# MainPCB.net
KiCad netlist of a schematic drawn in EAGLE
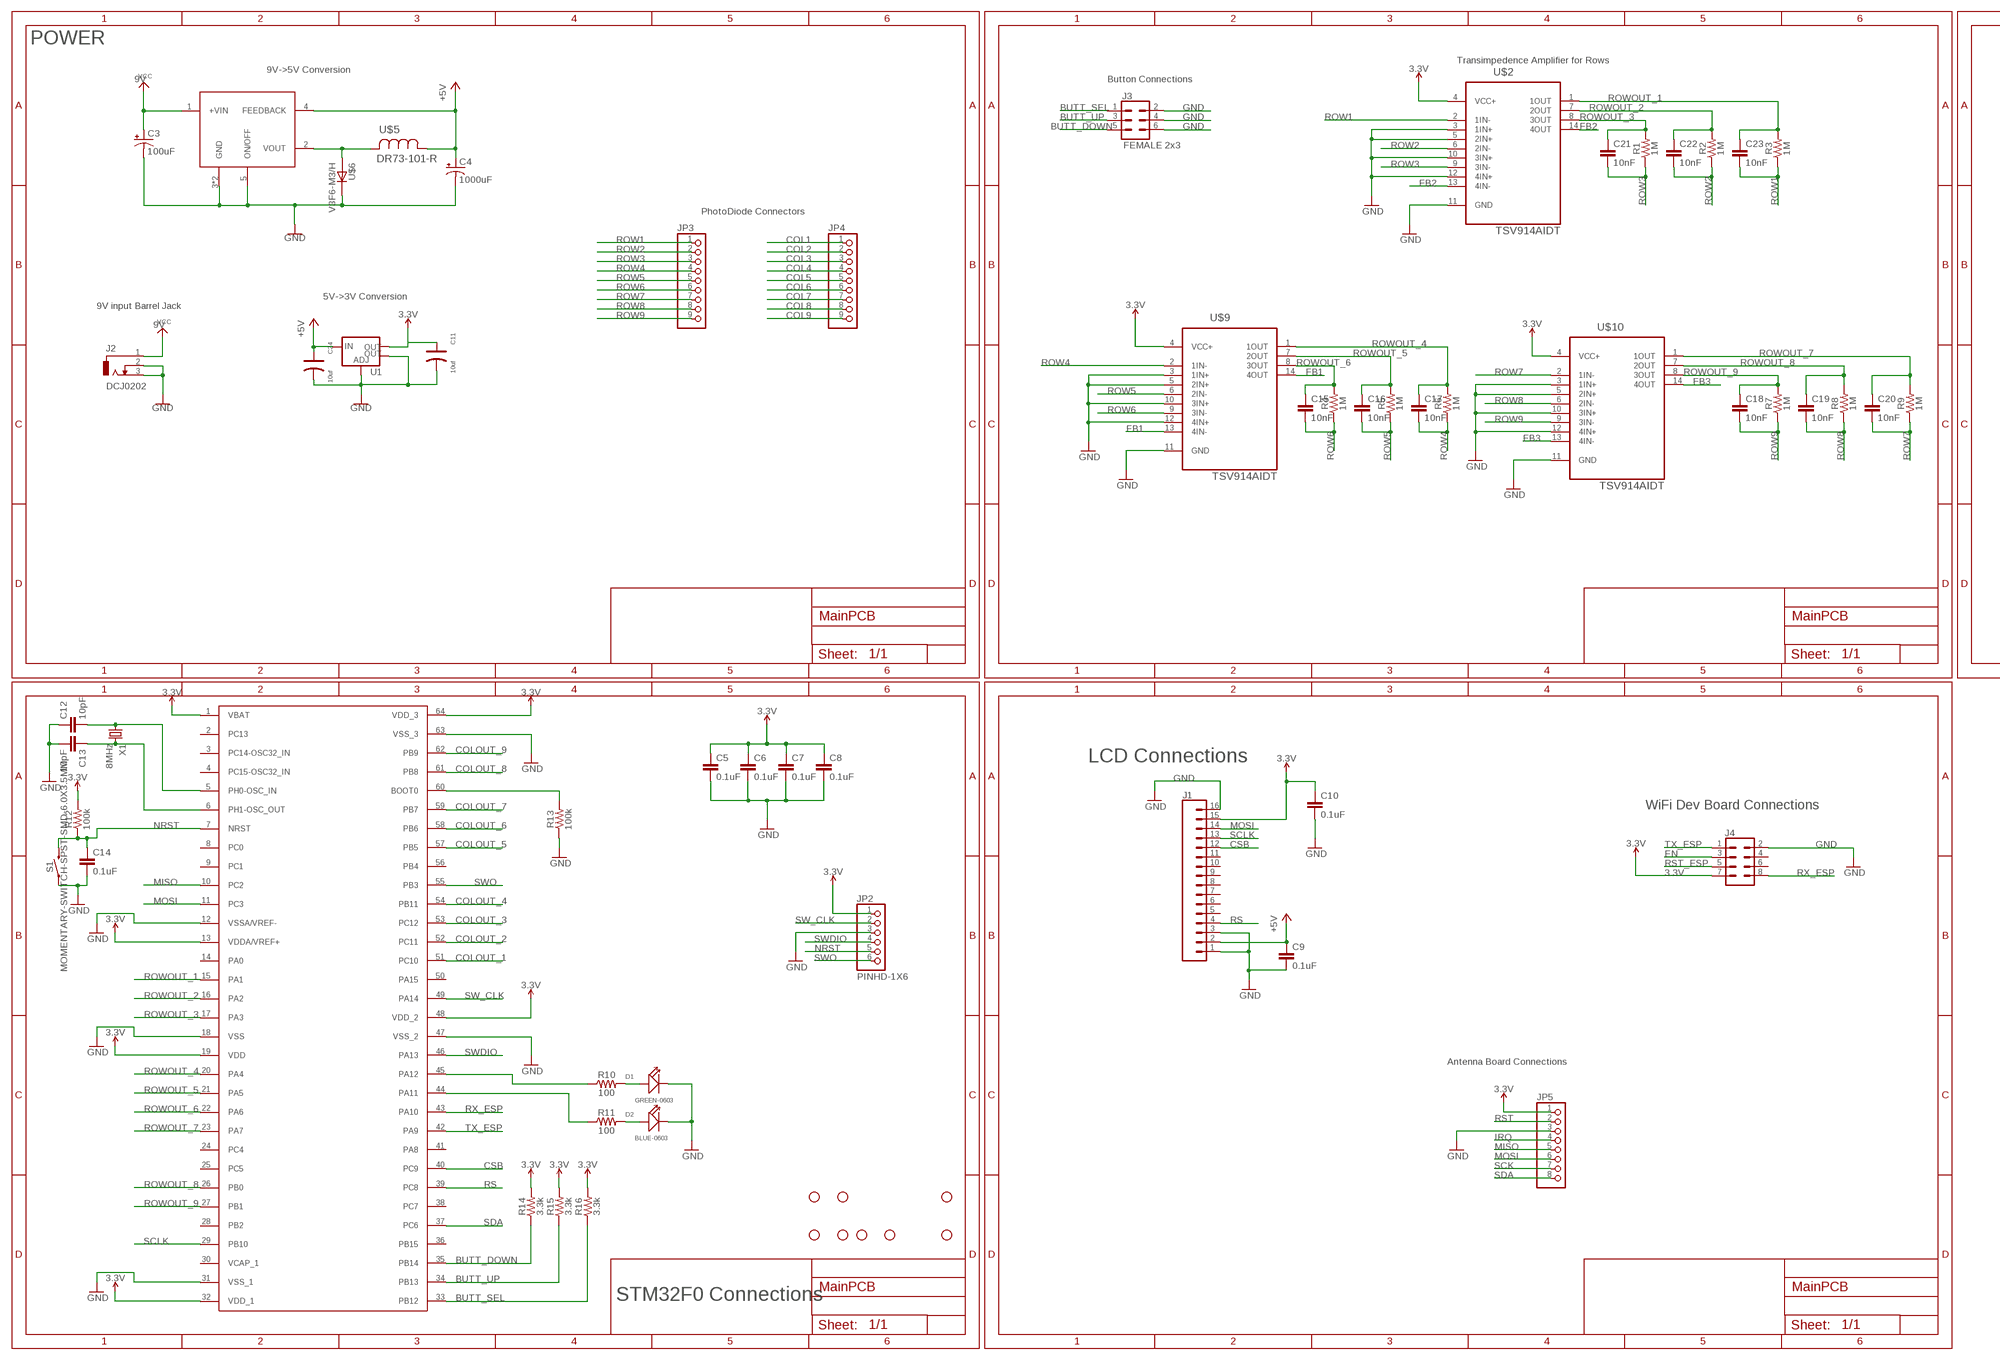
[diagram p0: schematic, sheet 1, part 1 of 2]
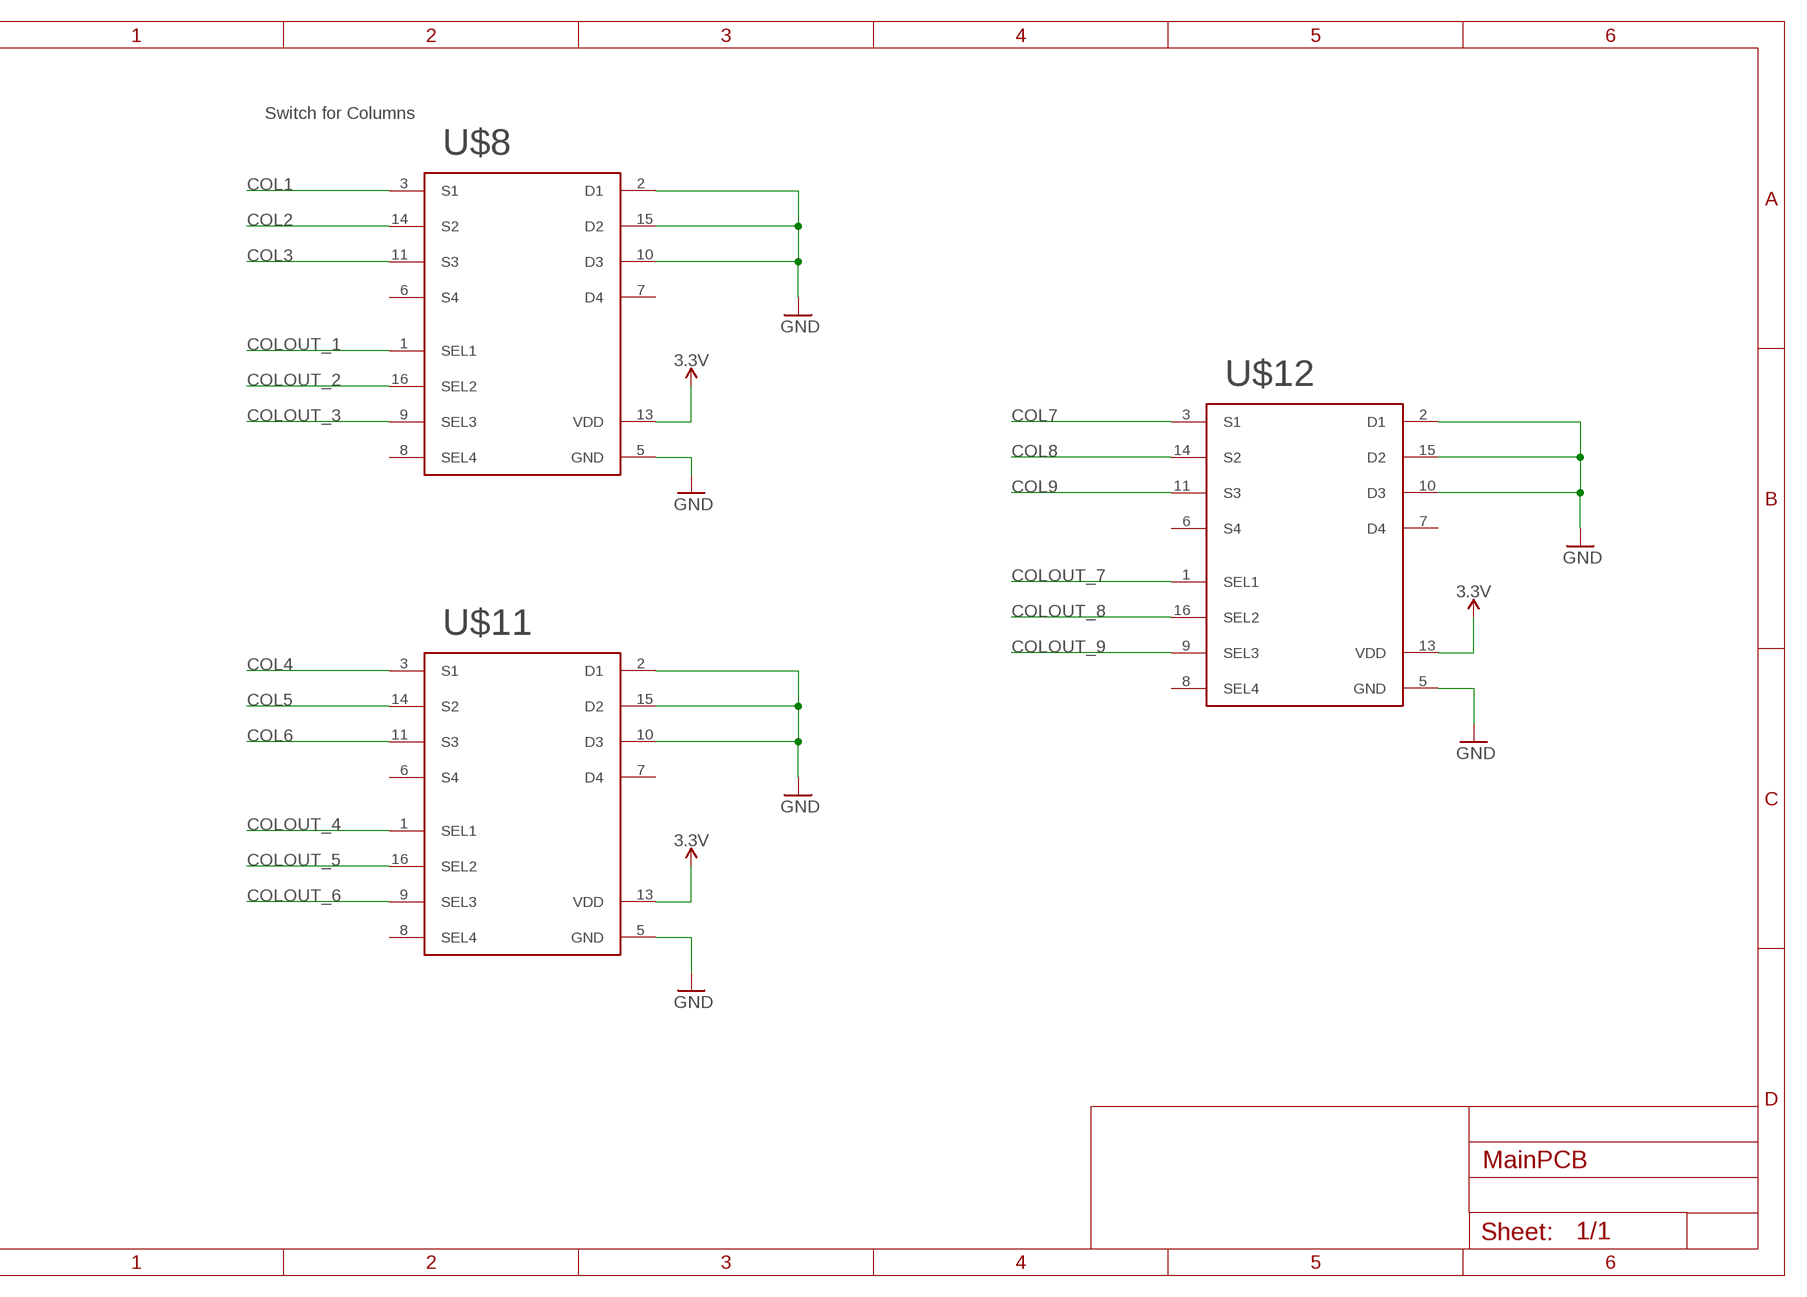
[diagram p1: schematic, sheet 1, part 2 of 2]

(export (version "E")
  (design (tool "Eeschema 10.0.6"))
  (components
    (comp (ref "C3")
      (value "100uF")
      (footprint "eagle-import:PANASONIC_D")
      (libsource (lib "eagle-import") (part "100UF-POLAR-25V-20%(ELEC)"))
    )
    (comp (ref "C4")
      (value "1000uF")
      (footprint "eagle-import:PANASONIC_D")
      (libsource (lib "eagle-import") (part "100UF-POLAR-25V-20%(ELEC)"))
    )
    (comp (ref "C5")
      (value "0.1uF")
      (footprint "eagle-import:0603")
      (libsource (lib "eagle-import") (part "0.1UF-0603-100V-10%"))
    )
    (comp (ref "C6")
      (value "0.1uF")
      (footprint "eagle-import:0603")
      (libsource (lib "eagle-import") (part "0.1UF-0603-100V-10%"))
    )
    (comp (ref "C7")
      (value "0.1uF")
      (footprint "eagle-import:0603")
      (libsource (lib "eagle-import") (part "0.1UF-0603-100V-10%"))
    )
    (comp (ref "C8")
      (value "0.1uF")
      (footprint "eagle-import:0603")
      (libsource (lib "eagle-import") (part "0.1UF-0603-100V-10%"))
    )
    (comp (ref "C9")
      (value "0.1uF")
      (footprint "eagle-import:0603")
      (libsource (lib "eagle-import") (part "0.1UF-0603-100V-10%"))
    )
    (comp (ref "C10")
      (value "0.1uF")
      (footprint "eagle-import:0603")
      (libsource (lib "eagle-import") (part "0.1UF-0603-100V-10%"))
    )
    (comp (ref "C11")
      (value "10uf")
      (footprint "eagle-import:AVX-A")
      (fields (field (name "MPN") "TAJA106K010RNJ"))
      (libsource (lib "eagle-import") (part "TANTALUM-SMD-10UF-10V-10%(AVX-A)"))
    )
    (comp (ref "C12")
      (value "10pF")
      (footprint "eagle-import:0805")
      (libsource (lib "eagle-import") (part "10UF-0805-10V-10%"))
    )
    (comp (ref "C13")
      (value "10pF")
      (footprint "eagle-import:0805")
      (libsource (lib "eagle-import") (part "10UF-0805-10V-10%"))
    )
    (comp (ref "C14")
      (value "0.1uF")
      (footprint "eagle-import:0603")
      (libsource (lib "eagle-import") (part "0.1UF-0603-25V-(+80/-20%)"))
    )
    (comp (ref "C15")
      (value "10nF")
      (footprint "eagle-import:0603")
      (libsource (lib "eagle-import") (part "10NF-0603-50V-10%"))
    )
    (comp (ref "C16")
      (value "10nF")
      (footprint "eagle-import:0603")
      (libsource (lib "eagle-import") (part "10NF-0603-50V-10%"))
    )
    (comp (ref "C17")
      (value "10nF")
      (footprint "eagle-import:0603")
      (libsource (lib "eagle-import") (part "10NF-0603-50V-10%"))
    )
    (comp (ref "C18")
      (value "10nF")
      (footprint "eagle-import:0603")
      (libsource (lib "eagle-import") (part "10NF-0603-50V-10%"))
    )
    (comp (ref "C19")
      (value "10nF")
      (footprint "eagle-import:0603")
      (libsource (lib "eagle-import") (part "10NF-0603-50V-10%"))
    )
    (comp (ref "C20")
      (value "10nF")
      (footprint "eagle-import:0603")
      (libsource (lib "eagle-import") (part "10NF-0603-50V-10%"))
    )
    (comp (ref "C21")
      (value "10nF")
      (footprint "eagle-import:0603")
      (libsource (lib "eagle-import") (part "10NF-0603-50V-10%"))
    )
    (comp (ref "C22")
      (value "10nF")
      (footprint "eagle-import:0603")
      (libsource (lib "eagle-import") (part "10NF-0603-50V-10%"))
    )
    (comp (ref "C23")
      (value "10nF")
      (footprint "eagle-import:0603")
      (libsource (lib "eagle-import") (part "10NF-0603-50V-10%"))
    )
    (comp (ref "C24")
      (value "10uf")
      (footprint "eagle-import:AVX-A")
      (fields (field (name "MPN") "TAJA106K010RNJ"))
      (libsource (lib "eagle-import") (part "TANTALUM-SMD-10UF-10V-10%(AVX-A)"))
    )
    (comp (ref "D1")
      (value "GREEN-0603")
      (footprint "eagle-import:LED-0603")
      (fields (field (name "MPN") "19-217-G7C-AN1P2-3T"))
      (libsource (lib "eagle-import") (part "SMD-LED-CLEAR-GREEN(0603)"))
    )
    (comp (ref "D2")
      (value "BLUE-0603")
      (footprint "eagle-import:LED-0603")
      (fields (field (name "MPN") "19-217-BHC-ZL1M2RY-3T"))
      (libsource (lib "eagle-import") (part "SMD-LED-CLEAR-BLUE(0603)"))
    )
    (comp (ref "H2")
      (value "STAND-OFF")
      (footprint "eagle-import:STAND-OFF")
      (libsource (lib "eagle-import") (part "STAND-OFF"))
    )
    (comp (ref "H3")
      (value "STAND-OFF")
      (footprint "eagle-import:STAND-OFF")
      (libsource (lib "eagle-import") (part "STAND-OFF"))
    )
    (comp (ref "H4")
      (value "STAND-OFF")
      (footprint "eagle-import:STAND-OFF")
      (libsource (lib "eagle-import") (part "STAND-OFF"))
    )
    (comp (ref "H6")
      (value "STAND-OFF")
      (footprint "eagle-import:STAND-OFF")
      (libsource (lib "eagle-import") (part "STAND-OFF"))
    )
    (comp (ref "H7")
      (value "STAND-OFF")
      (footprint "eagle-import:STAND-OFF")
      (libsource (lib "eagle-import") (part "STAND-OFF"))
    )
    (comp (ref "H8")
      (value "STAND-OFF")
      (footprint "eagle-import:STAND-OFF")
      (libsource (lib "eagle-import") (part "STAND-OFF"))
    )
    (comp (ref "H9")
      (value "STAND-OFF")
      (footprint "eagle-import:STAND-OFF")
      (libsource (lib "eagle-import") (part "STAND-OFF"))
    )
    (comp (ref "H10")
      (value "STAND-OFF")
      (footprint "eagle-import:STAND-OFF")
      (libsource (lib "eagle-import") (part "STAND-OFF"))
    )
    (comp (ref "J1")
      (value "CONN_161X16_NO_SILK")
      (footprint "eagle-import:1X16_NO_SILK")
      (libsource (lib "eagle-import") (part "CONN_161X16_NO_SILK"))
    )
    (comp (ref "J2")
      (value "DCJ0202")
      (footprint "eagle-import:DCJ0202")
      (libsource (lib "eagle-import") (part "DCJ0202"))
    )
    (comp (ref "J3")
      (value "FEMALE 2x3")
      (footprint "eagle-import:2X3")
      (libsource (lib "eagle-import") (part "CONN_03X2FEMALE"))
    )
    (comp (ref "J4")
      (value "CONN_04X2")
      (footprint "eagle-import:2X4")
      (libsource (lib "eagle-import") (part "CONN_04X2"))
    )
    (comp (ref "JP2")
      (value "PINHD-1X6")
      (footprint "eagle-import:1X06")
      (libsource (lib "eagle-import") (part "PINHD-1X6"))
    )
    (comp (ref "JP3")
      (value "PINHD-1X9")
      (footprint "eagle-import:1X09")
      (libsource (lib "eagle-import") (part "PINHD-1X9"))
    )
    (comp (ref "JP4")
      (value "PINHD-1X9")
      (footprint "eagle-import:1X09")
      (libsource (lib "eagle-import") (part "PINHD-1X9"))
    )
    (comp (ref "JP5")
      (value "PINHD-1X8")
      (footprint "eagle-import:1X08")
      (libsource (lib "eagle-import") (part "PINHD-1X8"))
    )
    (comp (ref "R1")
      (value "1M")
      (footprint "eagle-import:0603")
      (libsource (lib "eagle-import") (part "1KOHM-0603-1/10W-1%"))
    )
    (comp (ref "R2")
      (value "1M")
      (footprint "eagle-import:0603")
      (libsource (lib "eagle-import") (part "1KOHM-0603-1/10W-1%"))
    )
    (comp (ref "R3")
      (value "1M")
      (footprint "eagle-import:0603")
      (libsource (lib "eagle-import") (part "1KOHM-0603-1/10W-1%"))
    )
    (comp (ref "R4")
      (value "1M")
      (footprint "eagle-import:0603")
      (libsource (lib "eagle-import") (part "1KOHM-0603-1/10W-1%"))
    )
    (comp (ref "R5")
      (value "1M")
      (footprint "eagle-import:0603")
      (libsource (lib "eagle-import") (part "1KOHM-0603-1/10W-1%"))
    )
    (comp (ref "R6")
      (value "1M")
      (footprint "eagle-import:0603")
      (libsource (lib "eagle-import") (part "1KOHM-0603-1/10W-1%"))
    )
    (comp (ref "R7")
      (value "1M")
      (footprint "eagle-import:0603")
      (libsource (lib "eagle-import") (part "1KOHM-0603-1/10W-1%"))
    )
    (comp (ref "R8")
      (value "1M")
      (footprint "eagle-import:0603")
      (libsource (lib "eagle-import") (part "1KOHM-0603-1/10W-1%"))
    )
    (comp (ref "R9")
      (value "1M")
      (footprint "eagle-import:0603")
      (libsource (lib "eagle-import") (part "1KOHM-0603-1/10W-1%"))
    )
    (comp (ref "R10")
      (value "100")
      (footprint "eagle-import:0603")
      (libsource (lib "eagle-import") (part "100OHM-0603-1/4W-5%"))
    )
    (comp (ref "R11")
      (value "100")
      (footprint "eagle-import:0603")
      (libsource (lib "eagle-import") (part "100OHM-0603-1/4W-5%"))
    )
    (comp (ref "R12")
      (value "100k")
      (footprint "eagle-import:0603")
      (libsource (lib "eagle-import") (part "100KOHM-0603-1/10W-1%"))
    )
    (comp (ref "R13")
      (value "100k")
      (footprint "eagle-import:0603")
      (libsource (lib "eagle-import") (part "100KOHM-0603-1/10W-1%"))
    )
    (comp (ref "R14")
      (value "3.3k")
      (footprint "eagle-import:0603")
      (libsource (lib "eagle-import") (part "3.3KOHM-0603-1/10W-1%"))
    )
    (comp (ref "R15")
      (value "3.3k")
      (footprint "eagle-import:0603")
      (libsource (lib "eagle-import") (part "3.3KOHM-0603-1/10W-1%"))
    )
    (comp (ref "R16")
      (value "3.3k")
      (footprint "eagle-import:0603")
      (libsource (lib "eagle-import") (part "3.3KOHM-0603-1/10W-1%"))
    )
    (comp (ref "S1")
      (value "MOMENTARY-SWITCH-SPST-SMD-6.0X3.5MM")
      (footprint "eagle-import:TACTILE_SWITCH_SMD_6.0X3.5MM")
      (libsource (lib "eagle-import") (part "MOMENTARY-SWITCH-SPST-SMD-6.0X3.5MM"))
    )
    (comp (ref "U$1")
      (value "STM32F410R8T6")
      (footprint "eagle-import:TQFP64")
      (libsource (lib "eagle-import") (part "STM32F410R8T6"))
    )
    (comp (ref "U$2")
      (value "TSV914AIDT")
      (footprint "eagle-import:SOIC-14")
      (libsource (lib "eagle-import") (part "TSV914AIDT"))
    )
    (comp (ref "U$3")
      (value "LM2576")
      (footprint "eagle-import:DDPAK_TO-263-5")
      (libsource (lib "eagle-import") (part "LM2576"))
    )
    (comp (ref "U$5")
      (value "DR73-101-R")
      (footprint "eagle-import:INDUCTOR_NONSTANDARD")
      (libsource (lib "eagle-import") (part "DR73-101-R"))
    )
    (comp (ref "U$6")
      (value "V3F6-M3/H")
      (footprint "eagle-import:DO-219AB")
      (libsource (lib "eagle-import") (part "V3F6-M3/H"))
    )
    (comp (ref "U$8")
      (value "TMUX1112PWR")
      (footprint "eagle-import:16-TSSOP")
      (libsource (lib "eagle-import") (part "TMUX1112PWR"))
    )
    (comp (ref "U$9")
      (value "TSV914AIDT")
      (footprint "eagle-import:SOIC-14")
      (libsource (lib "eagle-import") (part "TSV914AIDT"))
    )
    (comp (ref "U$10")
      (value "TSV914AIDT")
      (footprint "eagle-import:SOIC-14")
      (libsource (lib "eagle-import") (part "TSV914AIDT"))
    )
    (comp (ref "U$11")
      (value "TMUX1112PWR")
      (footprint "eagle-import:16-TSSOP")
      (libsource (lib "eagle-import") (part "TMUX1112PWR"))
    )
    (comp (ref "U$12")
      (value "TMUX1112PWR")
      (footprint "eagle-import:16-TSSOP")
      (libsource (lib "eagle-import") (part "TMUX1112PWR"))
    )
    (comp (ref "U1")
      (value "V_REG_LM1117SOT223")
      (footprint "eagle-import:SOT223")
      (libsource (lib "eagle-import") (part "V_REG_LM1117SOT223"))
    )
    (comp (ref "X1")
      (value "8MHz")
      (footprint "eagle-import:HC49")
      (libsource (lib "eagle-import") (part "CRYSTALS-NOGND-HC49"))
    )
  )
  (nets
    (net (code "1") (name "+5V") (class "Default")
      (node (ref "C24") (pin "+") (pinfunction "+_+") (pintype "passive"))
      (node (ref "C4") (pin "+") (pinfunction "+_+") (pintype "passive"))
      (node (ref "C9") (pin "1") (pinfunction "1_1") (pintype "passive"))
      (node (ref "J1") (pin "2") (pinfunction "2_2") (pintype "passive"))
      (node (ref "U$3") (pin "4") (pinfunction "FEEDBACK_4") (pintype "bidirectional"))
      (node (ref "U$5") (pin "1") (pinfunction "1_1") (pintype "passive"))
      (node (ref "U1") (pin "3") (pinfunction "IN_3") (pintype "input"))
    )
    (net (code "2") (name "/BUTT_DOWN") (class "Default")
      (node (ref "J3") (pin "5") (pinfunction "5_5") (pintype "bidirectional"))
      (node (ref "R14") (pin "1") (pinfunction "1_1") (pintype "passive"))
      (node (ref "U$1") (pin "35") (pinfunction "PB14_35") (pintype "bidirectional"))
    )
    (net (code "3") (name "/BUTT_SEL") (class "Default")
      (node (ref "J3") (pin "1") (pinfunction "1_1") (pintype "bidirectional"))
      (node (ref "R16") (pin "1") (pinfunction "1_1") (pintype "passive"))
      (node (ref "U$1") (pin "33") (pinfunction "PB12_33") (pintype "bidirectional"))
    )
    (net (code "4") (name "/BUTT_UP") (class "Default")
      (node (ref "J3") (pin "3") (pinfunction "3_3") (pintype "bidirectional"))
      (node (ref "R15") (pin "1") (pinfunction "1_1") (pintype "passive"))
      (node (ref "U$1") (pin "34") (pinfunction "PB13_34") (pintype "bidirectional"))
    )
    (net (code "5") (name "/COL1") (class "Default")
      (node (ref "JP4") (pin "1") (pinfunction "1_1") (pintype "passive"))
      (node (ref "U$8") (pin "3") (pinfunction "S1_3") (pintype "bidirectional"))
    )
    (net (code "6") (name "/COL2") (class "Default")
      (node (ref "JP4") (pin "2") (pinfunction "2_2") (pintype "passive"))
      (node (ref "U$8") (pin "14") (pinfunction "S2_14") (pintype "bidirectional"))
    )
    (net (code "7") (name "/COL3") (class "Default")
      (node (ref "JP4") (pin "3") (pinfunction "3_3") (pintype "passive"))
      (node (ref "U$8") (pin "11") (pinfunction "S3_11") (pintype "bidirectional"))
    )
    (net (code "8") (name "/COL4") (class "Default")
      (node (ref "JP4") (pin "4") (pinfunction "4_4") (pintype "passive"))
      (node (ref "U$11") (pin "3") (pinfunction "S1_3") (pintype "bidirectional"))
    )
    (net (code "9") (name "/COL5") (class "Default")
      (node (ref "JP4") (pin "5") (pinfunction "5_5") (pintype "passive"))
      (node (ref "U$11") (pin "14") (pinfunction "S2_14") (pintype "bidirectional"))
    )
    (net (code "10") (name "/COL6") (class "Default")
      (node (ref "JP4") (pin "6") (pinfunction "6_6") (pintype "passive"))
      (node (ref "U$11") (pin "11") (pinfunction "S3_11") (pintype "bidirectional"))
    )
    (net (code "11") (name "/COL7") (class "Default")
      (node (ref "JP4") (pin "7") (pinfunction "7_7") (pintype "passive"))
      (node (ref "U$12") (pin "3") (pinfunction "S1_3") (pintype "bidirectional"))
    )
    (net (code "12") (name "/COL8") (class "Default")
      (node (ref "JP4") (pin "8") (pinfunction "8_8") (pintype "passive"))
      (node (ref "U$12") (pin "14") (pinfunction "S2_14") (pintype "bidirectional"))
    )
    (net (code "13") (name "/COL9") (class "Default")
      (node (ref "JP4") (pin "9") (pinfunction "9_9") (pintype "passive"))
      (node (ref "U$12") (pin "11") (pinfunction "S3_11") (pintype "bidirectional"))
    )
    (net (code "14") (name "/COLOUT_1") (class "Default")
      (node (ref "U$1") (pin "51") (pinfunction "PC10_51") (pintype "bidirectional"))
      (node (ref "U$8") (pin "1") (pinfunction "SEL1_1") (pintype "bidirectional"))
    )
    (net (code "15") (name "/COLOUT_2") (class "Default")
      (node (ref "U$1") (pin "52") (pinfunction "PC11_52") (pintype "bidirectional"))
      (node (ref "U$8") (pin "16") (pinfunction "SEL2_16") (pintype "bidirectional"))
    )
    (net (code "16") (name "/COLOUT_3") (class "Default")
      (node (ref "U$1") (pin "53") (pinfunction "PC12_53") (pintype "bidirectional"))
      (node (ref "U$8") (pin "9") (pinfunction "SEL3_9") (pintype "bidirectional"))
    )
    (net (code "17") (name "/COLOUT_4") (class "Default")
      (node (ref "U$1") (pin "54") (pinfunction "PB11_54") (pintype "bidirectional"))
      (node (ref "U$11") (pin "1") (pinfunction "SEL1_1") (pintype "bidirectional"))
    )
    (net (code "18") (name "/COLOUT_5") (class "Default")
      (node (ref "U$1") (pin "57") (pinfunction "PB5_57") (pintype "bidirectional"))
      (node (ref "U$11") (pin "16") (pinfunction "SEL2_16") (pintype "bidirectional"))
    )
    (net (code "19") (name "/COLOUT_6") (class "Default")
      (node (ref "U$1") (pin "58") (pinfunction "PB6_58") (pintype "bidirectional"))
      (node (ref "U$11") (pin "9") (pinfunction "SEL3_9") (pintype "bidirectional"))
    )
    (net (code "20") (name "/COLOUT_7") (class "Default")
      (node (ref "U$1") (pin "59") (pinfunction "PB7_59") (pintype "bidirectional"))
      (node (ref "U$12") (pin "1") (pinfunction "SEL1_1") (pintype "bidirectional"))
    )
    (net (code "21") (name "/COLOUT_8") (class "Default")
      (node (ref "U$1") (pin "61") (pinfunction "PB8_61") (pintype "bidirectional"))
      (node (ref "U$12") (pin "16") (pinfunction "SEL2_16") (pintype "bidirectional"))
    )
    (net (code "22") (name "/COLOUT_9") (class "Default")
      (node (ref "U$1") (pin "62") (pinfunction "PB9_62") (pintype "bidirectional"))
      (node (ref "U$12") (pin "9") (pinfunction "SEL3_9") (pintype "bidirectional"))
    )
    (net (code "23") (name "/CSB") (class "Default")
      (node (ref "J1") (pin "12") (pinfunction "12_12") (pintype "passive"))
      (node (ref "U$1") (pin "40") (pinfunction "PC9_40") (pintype "bidirectional"))
    )
    (net (code "24") (name "/EN") (class "Default")
      (node (ref "J4") (pin "3") (pinfunction "3_3") (pintype "passive"))
    )
    (net (code "25") (name "/FB1") (class "Default")
      (node (ref "U$9") (pin "13") (pinfunction "4IN-_13") (pintype "input"))
      (node (ref "U$9") (pin "14") (pinfunction "4OUT_14") (pintype "output"))
    )
    (net (code "26") (name "/FB2") (class "Default")
      (node (ref "U$2") (pin "13") (pinfunction "4IN-_13") (pintype "input"))
      (node (ref "U$2") (pin "14") (pinfunction "4OUT_14") (pintype "output"))
    )
    (net (code "27") (name "/FB3") (class "Default")
      (node (ref "U$10") (pin "13") (pinfunction "4IN-_13") (pintype "input"))
      (node (ref "U$10") (pin "14") (pinfunction "4OUT_14") (pintype "output"))
    )
    (net (code "28") (name "/IRQ") (class "Default")
      (node (ref "JP5") (pin "4") (pinfunction "4_4") (pintype "passive"))
    )
    (net (code "29") (name "/MISO") (class "Default")
      (node (ref "JP5") (pin "5") (pinfunction "5_5") (pintype "passive"))
      (node (ref "U$1") (pin "10") (pinfunction "PC2_10") (pintype "bidirectional"))
    )
    (net (code "30") (name "/MOSI") (class "Default")
      (node (ref "J1") (pin "14") (pinfunction "14_14") (pintype "passive"))
      (node (ref "JP5") (pin "6") (pinfunction "6_6") (pintype "passive"))
      (node (ref "U$1") (pin "11") (pinfunction "PC3_11") (pintype "bidirectional"))
    )
    (net (code "31") (name "/NRST") (class "Default")
      (node (ref "C14") (pin "1") (pinfunction "1_1") (pintype "passive"))
      (node (ref "JP2") (pin "5") (pinfunction "5_5") (pintype "passive"))
      (node (ref "R12") (pin "1") (pinfunction "1_1") (pintype "passive"))
      (node (ref "S1") (pin "2") (pinfunction "2_2") (pintype "passive"))
      (node (ref "U$1") (pin "7") (pinfunction "NRST_7") (pintype "bidirectional"))
    )
    (net (code "32") (name "/ROW1") (class "Default")
      (node (ref "C23") (pin "2") (pinfunction "2_2") (pintype "passive"))
      (node (ref "JP3") (pin "1") (pinfunction "1_1") (pintype "passive"))
      (node (ref "R3") (pin "1") (pinfunction "1_1") (pintype "passive"))
      (node (ref "U$2") (pin "2") (pinfunction "1IN-_2") (pintype "input"))
    )
    (net (code "33") (name "/ROW2") (class "Default")
      (node (ref "C22") (pin "2") (pinfunction "2_2") (pintype "passive"))
      (node (ref "JP3") (pin "2") (pinfunction "2_2") (pintype "passive"))
      (node (ref "R2") (pin "1") (pinfunction "1_1") (pintype "passive"))
      (node (ref "U$2") (pin "6") (pinfunction "2IN-_6") (pintype "input"))
    )
    (net (code "34") (name "/ROW3") (class "Default")
      (node (ref "C21") (pin "2") (pinfunction "2_2") (pintype "passive"))
      (node (ref "JP3") (pin "3") (pinfunction "3_3") (pintype "passive"))
      (node (ref "R1") (pin "1") (pinfunction "1_1") (pintype "passive"))
      (node (ref "U$2") (pin "9") (pinfunction "3IN-_9") (pintype "input"))
    )
    (net (code "35") (name "/ROW4") (class "Default")
      (node (ref "C17") (pin "2") (pinfunction "2_2") (pintype "passive"))
      (node (ref "JP3") (pin "4") (pinfunction "4_4") (pintype "passive"))
      (node (ref "R6") (pin "1") (pinfunction "1_1") (pintype "passive"))
      (node (ref "U$9") (pin "2") (pinfunction "1IN-_2") (pintype "input"))
    )
    (net (code "36") (name "/ROW5") (class "Default")
      (node (ref "C16") (pin "2") (pinfunction "2_2") (pintype "passive"))
      (node (ref "JP3") (pin "5") (pinfunction "5_5") (pintype "passive"))
      (node (ref "R5") (pin "1") (pinfunction "1_1") (pintype "passive"))
      (node (ref "U$9") (pin "6") (pinfunction "2IN-_6") (pintype "input"))
    )
    (net (code "37") (name "/ROW6") (class "Default")
      (node (ref "C15") (pin "2") (pinfunction "2_2") (pintype "passive"))
      (node (ref "JP3") (pin "6") (pinfunction "6_6") (pintype "passive"))
      (node (ref "R4") (pin "1") (pinfunction "1_1") (pintype "passive"))
      (node (ref "U$9") (pin "9") (pinfunction "3IN-_9") (pintype "input"))
    )
    (net (code "38") (name "/ROW7") (class "Default")
      (node (ref "C20") (pin "2") (pinfunction "2_2") (pintype "passive"))
      (node (ref "JP3") (pin "7") (pinfunction "7_7") (pintype "passive"))
      (node (ref "R9") (pin "1") (pinfunction "1_1") (pintype "passive"))
      (node (ref "U$10") (pin "2") (pinfunction "1IN-_2") (pintype "input"))
    )
    (net (code "39") (name "/ROW8") (class "Default")
      (node (ref "C19") (pin "2") (pinfunction "2_2") (pintype "passive"))
      (node (ref "JP3") (pin "8") (pinfunction "8_8") (pintype "passive"))
      (node (ref "R8") (pin "1") (pinfunction "1_1") (pintype "passive"))
      (node (ref "U$10") (pin "6") (pinfunction "2IN-_6") (pintype "input"))
    )
    (net (code "40") (name "/ROW9") (class "Default")
      (node (ref "C18") (pin "2") (pinfunction "2_2") (pintype "passive"))
      (node (ref "JP3") (pin "9") (pinfunction "9_9") (pintype "passive"))
      (node (ref "R7") (pin "1") (pinfunction "1_1") (pintype "passive"))
      (node (ref "U$10") (pin "9") (pinfunction "3IN-_9") (pintype "input"))
    )
    (net (code "41") (name "/ROWOUT_1") (class "Default")
      (node (ref "C23") (pin "1") (pinfunction "1_1") (pintype "passive"))
      (node (ref "R3") (pin "2") (pinfunction "2_2") (pintype "passive"))
      (node (ref "U$1") (pin "15") (pinfunction "PA1_15") (pintype "bidirectional"))
      (node (ref "U$2") (pin "1") (pinfunction "1OUT_1") (pintype "output"))
    )
    (net (code "42") (name "/ROWOUT_2") (class "Default")
      (node (ref "C22") (pin "1") (pinfunction "1_1") (pintype "passive"))
      (node (ref "R2") (pin "2") (pinfunction "2_2") (pintype "passive"))
      (node (ref "U$1") (pin "16") (pinfunction "PA2_16") (pintype "bidirectional"))
      (node (ref "U$2") (pin "7") (pinfunction "2OUT_7") (pintype "output"))
    )
    (net (code "43") (name "/ROWOUT_3") (class "Default")
      (node (ref "C21") (pin "1") (pinfunction "1_1") (pintype "passive"))
      (node (ref "R1") (pin "2") (pinfunction "2_2") (pintype "passive"))
      (node (ref "U$1") (pin "17") (pinfunction "PA3_17") (pintype "bidirectional"))
      (node (ref "U$2") (pin "8") (pinfunction "3OUT_8") (pintype "output"))
    )
    (net (code "44") (name "/ROWOUT_4") (class "Default")
      (node (ref "C17") (pin "1") (pinfunction "1_1") (pintype "passive"))
      (node (ref "R6") (pin "2") (pinfunction "2_2") (pintype "passive"))
      (node (ref "U$1") (pin "20") (pinfunction "PA4_20") (pintype "bidirectional"))
      (node (ref "U$9") (pin "1") (pinfunction "1OUT_1") (pintype "output"))
    )
    (net (code "45") (name "/ROWOUT_5") (class "Default")
      (node (ref "C16") (pin "1") (pinfunction "1_1") (pintype "passive"))
      (node (ref "R5") (pin "2") (pinfunction "2_2") (pintype "passive"))
      (node (ref "U$1") (pin "21") (pinfunction "PA5_21") (pintype "bidirectional"))
      (node (ref "U$9") (pin "7") (pinfunction "2OUT_7") (pintype "output"))
    )
    (net (code "46") (name "/ROWOUT_6") (class "Default")
      (node (ref "C15") (pin "1") (pinfunction "1_1") (pintype "passive"))
      (node (ref "R4") (pin "2") (pinfunction "2_2") (pintype "passive"))
      (node (ref "U$1") (pin "22") (pinfunction "PA6_22") (pintype "bidirectional"))
      (node (ref "U$9") (pin "8") (pinfunction "3OUT_8") (pintype "output"))
    )
    (net (code "47") (name "/ROWOUT_7") (class "Default")
      (node (ref "C20") (pin "1") (pinfunction "1_1") (pintype "passive"))
      (node (ref "R9") (pin "2") (pinfunction "2_2") (pintype "passive"))
      (node (ref "U$1") (pin "23") (pinfunction "PA7_23") (pintype "bidirectional"))
      (node (ref "U$10") (pin "1") (pinfunction "1OUT_1") (pintype "output"))
    )
    (net (code "48") (name "/ROWOUT_8") (class "Default")
      (node (ref "C19") (pin "1") (pinfunction "1_1") (pintype "passive"))
      (node (ref "R8") (pin "2") (pinfunction "2_2") (pintype "passive"))
      (node (ref "U$1") (pin "26") (pinfunction "PB0_26") (pintype "bidirectional"))
      (node (ref "U$10") (pin "7") (pinfunction "2OUT_7") (pintype "output"))
    )
    (net (code "49") (name "/ROWOUT_9") (class "Default")
      (node (ref "C18") (pin "1") (pinfunction "1_1") (pintype "passive"))
      (node (ref "R7") (pin "2") (pinfunction "2_2") (pintype "passive"))
      (node (ref "U$1") (pin "27") (pinfunction "PB1_27") (pintype "bidirectional"))
      (node (ref "U$10") (pin "8") (pinfunction "3OUT_8") (pintype "output"))
    )
    (net (code "50") (name "/RS") (class "Default")
      (node (ref "J1") (pin "4") (pinfunction "4_4") (pintype "passive"))
      (node (ref "U$1") (pin "39") (pinfunction "PC8_39") (pintype "bidirectional"))
    )
    (net (code "51") (name "/RST") (class "Default")
      (node (ref "JP5") (pin "2") (pinfunction "2_2") (pintype "passive"))
    )
    (net (code "52") (name "/RST_ESP") (class "Default")
      (node (ref "J4") (pin "5") (pinfunction "5_5") (pintype "passive"))
    )
    (net (code "53") (name "/RX_ESP") (class "Default")
      (node (ref "J4") (pin "8") (pinfunction "8_8") (pintype "passive"))
      (node (ref "U$1") (pin "43") (pinfunction "PA10_43") (pintype "bidirectional"))
    )
    (net (code "54") (name "/SCK") (class "Default")
      (node (ref "JP5") (pin "7") (pinfunction "7_7") (pintype "passive"))
    )
    (net (code "55") (name "/SCLK") (class "Default")
      (node (ref "J1") (pin "13") (pinfunction "13_13") (pintype "passive"))
      (node (ref "U$1") (pin "29") (pinfunction "PB10_29") (pintype "bidirectional"))
    )
    (net (code "56") (name "/SDA") (class "Default")
      (node (ref "JP5") (pin "8") (pinfunction "8_8") (pintype "passive"))
      (node (ref "U$1") (pin "37") (pinfunction "PC6_37") (pintype "bidirectional"))
    )
    (net (code "57") (name "/SWDIO") (class "Default")
      (node (ref "JP2") (pin "4") (pinfunction "4_4") (pintype "passive"))
      (node (ref "U$1") (pin "46") (pinfunction "PA13_46") (pintype "bidirectional"))
    )
    (net (code "58") (name "/SWO") (class "Default")
      (node (ref "JP2") (pin "6") (pinfunction "6_6") (pintype "passive"))
      (node (ref "U$1") (pin "55") (pinfunction "PB3_55") (pintype "bidirectional"))
    )
    (net (code "59") (name "/SW_CLK") (class "Default")
      (node (ref "JP2") (pin "2") (pinfunction "2_2") (pintype "passive"))
      (node (ref "U$1") (pin "49") (pinfunction "PA14_49") (pintype "bidirectional"))
    )
    (net (code "60") (name "/TX_ESP") (class "Default")
      (node (ref "J4") (pin "1") (pinfunction "1_1") (pintype "passive"))
      (node (ref "U$1") (pin "42") (pinfunction "PA9_42") (pintype "bidirectional"))
    )
    (net (code "61") (name "3.3V") (class "Default")
      (node (ref "C10") (pin "1") (pinfunction "1_1") (pintype "passive"))
      (node (ref "C11") (pin "+") (pinfunction "+_+") (pintype "passive"))
      (node (ref "C5") (pin "1") (pinfunction "1_1") (pintype "passive"))
      (node (ref "C6") (pin "1") (pinfunction "1_1") (pintype "passive"))
      (node (ref "C7") (pin "1") (pinfunction "1_1") (pintype "passive"))
      (node (ref "C8") (pin "1") (pinfunction "1_1") (pintype "passive"))
      (node (ref "J1") (pin "15") (pinfunction "15_15") (pintype "passive"))
      (node (ref "J4") (pin "7") (pinfunction "7_7") (pintype "passive"))
      (node (ref "JP2") (pin "1") (pinfunction "1_1") (pintype "passive"))
      (node (ref "JP5") (pin "1") (pinfunction "1_1") (pintype "passive"))
      (node (ref "R12") (pin "2") (pinfunction "2_2") (pintype "passive"))
      (node (ref "R14") (pin "2") (pinfunction "2_2") (pintype "passive"))
      (node (ref "R15") (pin "2") (pinfunction "2_2") (pintype "passive"))
      (node (ref "R16") (pin "2") (pinfunction "2_2") (pintype "passive"))
      (node (ref "U$1") (pin "1") (pinfunction "VBAT_1") (pintype "bidirectional"))
      (node (ref "U$1") (pin "13") (pinfunction "VDDA/VREF+_13") (pintype "bidirectional"))
      (node (ref "U$1") (pin "19") (pinfunction "VDD_19") (pintype "bidirectional"))
      (node (ref "U$1") (pin "32") (pinfunction "VDD_1_32") (pintype "bidirectional"))
      (node (ref "U$1") (pin "48") (pinfunction "VDD_2_48") (pintype "bidirectional"))
      (node (ref "U$1") (pin "64") (pinfunction "VDD_3_64") (pintype "bidirectional"))
      (node (ref "U$10") (pin "4") (pinfunction "VCC+_4") (pintype "power_in"))
      (node (ref "U$11") (pin "13") (pinfunction "VDD_13") (pintype "bidirectional"))
      (node (ref "U$12") (pin "13") (pinfunction "VDD_13") (pintype "bidirectional"))
      (node (ref "U$2") (pin "4") (pinfunction "VCC+_4") (pintype "power_in"))
      (node (ref "U$8") (pin "13") (pinfunction "VDD_13") (pintype "bidirectional"))
      (node (ref "U$9") (pin "4") (pinfunction "VCC+_4") (pintype "power_in"))
      (node (ref "U1") (pin "2") (pinfunction "OUT_2") (pintype "output"))
    )
    (net (code "62") (name "GND") (class "Default")
      (node (ref "C10") (pin "2") (pinfunction "2_2") (pintype "passive"))
      (node (ref "C11") (pin "-") (pinfunction "-_-") (pintype "passive"))
      (node (ref "C12") (pin "1") (pinfunction "1_1") (pintype "passive"))
      (node (ref "C13") (pin "2") (pinfunction "2_2") (pintype "passive"))
      (node (ref "C14") (pin "2") (pinfunction "2_2") (pintype "passive"))
      (node (ref "C24") (pin "-") (pinfunction "-_-") (pintype "passive"))
      (node (ref "C3") (pin "-") (pinfunction "-_-") (pintype "passive"))
      (node (ref "C4") (pin "-") (pinfunction "-_-") (pintype "passive"))
      (node (ref "C5") (pin "2") (pinfunction "2_2") (pintype "passive"))
      (node (ref "C6") (pin "2") (pinfunction "2_2") (pintype "passive"))
      (node (ref "C7") (pin "2") (pinfunction "2_2") (pintype "passive"))
      (node (ref "C8") (pin "2") (pinfunction "2_2") (pintype "passive"))
      (node (ref "C9") (pin "2") (pinfunction "2_2") (pintype "passive"))
      (node (ref "D1") (pin "-") (pinfunction "-_-") (pintype "passive"))
      (node (ref "D2") (pin "-") (pinfunction "-_-") (pintype "passive"))
      (node (ref "J1") (pin "1") (pinfunction "1_1") (pintype "passive"))
      (node (ref "J1") (pin "16") (pinfunction "16_16") (pintype "passive"))
      (node (ref "J1") (pin "3") (pinfunction "3_3") (pintype "passive"))
      (node (ref "J2") (pin "2") (pinfunction "2_2") (pintype "passive"))
      (node (ref "J2") (pin "3") (pinfunction "3_3") (pintype "passive"))
      (node (ref "J3") (pin "2") (pinfunction "2_2") (pintype "bidirectional"))
      (node (ref "J3") (pin "4") (pinfunction "4_4") (pintype "bidirectional"))
      (node (ref "J3") (pin "6") (pinfunction "6_6") (pintype "bidirectional"))
      (node (ref "J4") (pin "2") (pinfunction "2_2") (pintype "passive"))
      (node (ref "JP2") (pin "3") (pinfunction "3_3") (pintype "passive"))
      (node (ref "JP5") (pin "3") (pinfunction "3_3") (pintype "passive"))
      (node (ref "R13") (pin "1") (pinfunction "1_1") (pintype "passive"))
      (node (ref "S1") (pin "1") (pinfunction "1_1") (pintype "passive"))
      (node (ref "U$1") (pin "12") (pinfunction "VSSA/VREF-_12") (pintype "bidirectional"))
      (node (ref "U$1") (pin "18") (pinfunction "VSS_18") (pintype "bidirectional"))
      (node (ref "U$1") (pin "31") (pinfunction "VSS_1_31") (pintype "bidirectional"))
      (node (ref "U$1") (pin "47") (pinfunction "VSS_2_47") (pintype "bidirectional"))
      (node (ref "U$1") (pin "63") (pinfunction "VSS_3_63") (pintype "bidirectional"))
      (node (ref "U$10") (pin "10") (pinfunction "3IN+_10") (pintype "input"))
      (node (ref "U$10") (pin "11") (pinfunction "GND_11") (pintype "passive"))
      (node (ref "U$10") (pin "12") (pinfunction "4IN+_12") (pintype "input"))
      (node (ref "U$10") (pin "3") (pinfunction "1IN+_3") (pintype "input"))
      (node (ref "U$10") (pin "5") (pinfunction "2IN+_5") (pintype "input"))
      (node (ref "U$11") (pin "10") (pinfunction "D3_10") (pintype "bidirectional"))
      (node (ref "U$11") (pin "15") (pinfunction "D2_15") (pintype "bidirectional"))
      (node (ref "U$11") (pin "2") (pinfunction "D1_2") (pintype "bidirectional"))
      (node (ref "U$11") (pin "5") (pinfunction "GND_5") (pintype "bidirectional"))
      (node (ref "U$12") (pin "10") (pinfunction "D3_10") (pintype "bidirectional"))
      (node (ref "U$12") (pin "15") (pinfunction "D2_15") (pintype "bidirectional"))
      (node (ref "U$12") (pin "2") (pinfunction "D1_2") (pintype "bidirectional"))
      (node (ref "U$12") (pin "5") (pinfunction "GND_5") (pintype "bidirectional"))
      (node (ref "U$2") (pin "10") (pinfunction "3IN+_10") (pintype "input"))
      (node (ref "U$2") (pin "11") (pinfunction "GND_11") (pintype "passive"))
      (node (ref "U$2") (pin "12") (pinfunction "4IN+_12") (pintype "input"))
      (node (ref "U$2") (pin "3") (pinfunction "1IN+_3") (pintype "input"))
      (node (ref "U$2") (pin "5") (pinfunction "2IN+_5") (pintype "input"))
      (node (ref "U$3") (pin "3") (pinfunction "GND_3") (pintype "bidirectional"))
      (node (ref "U$3") (pin "5") (pinfunction "ON/OFF_5") (pintype "bidirectional"))
      (node (ref "U$3") (pin "6") (pinfunction "GND_6") (pintype "bidirectional"))
      (node (ref "U$6") (pin "C") (pinfunction "C_C") (pintype "passive"))
      (node (ref "U$8") (pin "10") (pinfunction "D3_10") (pintype "bidirectional"))
      (node (ref "U$8") (pin "15") (pinfunction "D2_15") (pintype "bidirectional"))
      (node (ref "U$8") (pin "2") (pinfunction "D1_2") (pintype "bidirectional"))
      (node (ref "U$8") (pin "5") (pinfunction "GND_5") (pintype "bidirectional"))
      (node (ref "U$9") (pin "10") (pinfunction "3IN+_10") (pintype "input"))
      (node (ref "U$9") (pin "11") (pinfunction "GND_11") (pintype "passive"))
      (node (ref "U$9") (pin "12") (pinfunction "4IN+_12") (pintype "input"))
      (node (ref "U$9") (pin "3") (pinfunction "1IN+_3") (pintype "input"))
      (node (ref "U$9") (pin "5") (pinfunction "2IN+_5") (pintype "input"))
      (node (ref "U1") (pin "1") (pinfunction "ADJ_1") (pintype "input"))
      (node (ref "U1") (pin "4") (pinfunction "OUT_4") (pintype "output"))
    )
    (net (code "63") (name "Net-(D1-Pad+)") (class "Default")
      (node (ref "D1") (pin "+") (pinfunction "+_+") (pintype "passive"))
      (node (ref "R10") (pin "2") (pinfunction "2_2") (pintype "passive"))
    )
    (net (code "64") (name "Net-(D2-Pad+)") (class "Default")
      (node (ref "D2") (pin "+") (pinfunction "+_+") (pintype "passive"))
      (node (ref "R11") (pin "2") (pinfunction "2_2") (pintype "passive"))
    )
    (net (code "65") (name "Net-(U$1-BOOT0)") (class "Default")
      (node (ref "R13") (pin "2") (pinfunction "2_2") (pintype "passive"))
      (node (ref "U$1") (pin "60") (pinfunction "BOOT0_60") (pintype "bidirectional"))
    )
    (net (code "66") (name "Net-(U$1-PA11)") (class "Default")
      (node (ref "R11") (pin "1") (pinfunction "1_1") (pintype "passive"))
      (node (ref "U$1") (pin "44") (pinfunction "PA11_44") (pintype "bidirectional"))
    )
    (net (code "67") (name "Net-(U$1-PA12)") (class "Default")
      (node (ref "R10") (pin "1") (pinfunction "1_1") (pintype "passive"))
      (node (ref "U$1") (pin "45") (pinfunction "PA12_45") (pintype "bidirectional"))
    )
    (net (code "68") (name "Net-(U$1-PH0-OSC_IN)") (class "Default")
      (node (ref "C12") (pin "2") (pinfunction "2_2") (pintype "passive"))
      (node (ref "U$1") (pin "5") (pinfunction "PH0-OSC_IN_5") (pintype "bidirectional"))
      (node (ref "X1") (pin "1") (pinfunction "1_1") (pintype "passive"))
    )
    (net (code "69") (name "Net-(U$1-PH1-OSC_OUT)") (class "Default")
      (node (ref "C13") (pin "1") (pinfunction "1_1") (pintype "passive"))
      (node (ref "U$1") (pin "6") (pinfunction "PH1-OSC_OUT_6") (pintype "bidirectional"))
      (node (ref "X1") (pin "2") (pinfunction "2_2") (pintype "passive"))
    )
    (net (code "70") (name "Net-(U$3-VOUT)") (class "Default")
      (node (ref "U$3") (pin "2") (pinfunction "VOUT_2") (pintype "bidirectional"))
      (node (ref "U$5") (pin "2") (pinfunction "2_2") (pintype "passive"))
      (node (ref "U$6") (pin "A") (pinfunction "A_A") (pintype "passive"))
    )
    (net (code "71") (name "VCC") (class "Default")
      (node (ref "C3") (pin "+") (pinfunction "+_+") (pintype "passive"))
      (node (ref "J2") (pin "1") (pinfunction "1_1") (pintype "passive"))
      (node (ref "U$3") (pin "1") (pinfunction "+VIN_1") (pintype "bidirectional"))
    )
    (net (code "72") (name "unconnected-(J1-Pad5)") (class "Default")
      (node (ref "J1") (pin "5") (pinfunction "5_5") (pintype "passive"))
    )
    (net (code "73") (name "unconnected-(J1-Pad6)") (class "Default")
      (node (ref "J1") (pin "6") (pinfunction "6_6") (pintype "passive"))
    )
    (net (code "74") (name "unconnected-(J1-Pad7)") (class "Default")
      (node (ref "J1") (pin "7") (pinfunction "7_7") (pintype "passive"))
    )
    (net (code "75") (name "unconnected-(J1-Pad8)") (class "Default")
      (node (ref "J1") (pin "8") (pinfunction "8_8") (pintype "passive"))
    )
    (net (code "76") (name "unconnected-(J1-Pad9)") (class "Default")
      (node (ref "J1") (pin "9") (pinfunction "9_9") (pintype "passive"))
    )
    (net (code "77") (name "unconnected-(J1-Pad10)") (class "Default")
      (node (ref "J1") (pin "10") (pinfunction "10_10") (pintype "passive"))
    )
    (net (code "78") (name "unconnected-(J1-Pad11)") (class "Default")
      (node (ref "J1") (pin "11") (pinfunction "11_11") (pintype "passive"))
    )
    (net (code "79") (name "unconnected-(J4-Pad4)") (class "Default")
      (node (ref "J4") (pin "4") (pinfunction "4_4") (pintype "passive"))
    )
    (net (code "80") (name "unconnected-(J4-Pad6)") (class "Default")
      (node (ref "J4") (pin "6") (pinfunction "6_6") (pintype "passive"))
    )
    (net (code "81") (name "unconnected-(U$1-PA0-Pad14)") (class "Default")
      (node (ref "U$1") (pin "14") (pinfunction "PA0_14") (pintype "bidirectional"))
    )
    (net (code "82") (name "unconnected-(U$1-PA8-Pad41)") (class "Default")
      (node (ref "U$1") (pin "41") (pinfunction "PA8_41") (pintype "bidirectional"))
    )
    (net (code "83") (name "unconnected-(U$1-PA15-Pad50)") (class "Default")
      (node (ref "U$1") (pin "50") (pinfunction "PA15_50") (pintype "bidirectional"))
    )
    (net (code "84") (name "unconnected-(U$1-PB2-Pad28)") (class "Default")
      (node (ref "U$1") (pin "28") (pinfunction "PB2_28") (pintype "bidirectional"))
    )
    (net (code "85") (name "unconnected-(U$1-PB4-Pad56)") (class "Default")
      (node (ref "U$1") (pin "56") (pinfunction "PB4_56") (pintype "bidirectional"))
    )
    (net (code "86") (name "unconnected-(U$1-PB15-Pad36)") (class "Default")
      (node (ref "U$1") (pin "36") (pinfunction "PB15_36") (pintype "bidirectional"))
    )
    (net (code "87") (name "unconnected-(U$1-PC0-Pad8)") (class "Default")
      (node (ref "U$1") (pin "8") (pinfunction "PC0_8") (pintype "bidirectional"))
    )
    (net (code "88") (name "unconnected-(U$1-PC1-Pad9)") (class "Default")
      (node (ref "U$1") (pin "9") (pinfunction "PC1_9") (pintype "bidirectional"))
    )
    (net (code "89") (name "unconnected-(U$1-PC4-Pad24)") (class "Default")
      (node (ref "U$1") (pin "24") (pinfunction "PC4_24") (pintype "bidirectional"))
    )
    (net (code "90") (name "unconnected-(U$1-PC5-Pad25)") (class "Default")
      (node (ref "U$1") (pin "25") (pinfunction "PC5_25") (pintype "bidirectional"))
    )
    (net (code "91") (name "unconnected-(U$1-PC7-Pad38)") (class "Default")
      (node (ref "U$1") (pin "38") (pinfunction "PC7_38") (pintype "bidirectional"))
    )
    (net (code "92") (name "unconnected-(U$1-PC13-Pad2)") (class "Default")
      (node (ref "U$1") (pin "2") (pinfunction "PC13_2") (pintype "bidirectional"))
    )
    (net (code "93") (name "unconnected-(U$1-PC14-OSC32_IN-Pad3)") (class "Default")
      (node (ref "U$1") (pin "3") (pinfunction "PC14-OSC32_IN_3") (pintype "bidirectional"))
    )
    (net (code "94") (name "unconnected-(U$1-PC15-OSC32_IN-Pad4)") (class "Default")
      (node (ref "U$1") (pin "4") (pinfunction "PC15-OSC32_IN_4") (pintype "bidirectional"))
    )
    (net (code "95") (name "unconnected-(U$1-VCAP_1-Pad30)") (class "Default")
      (node (ref "U$1") (pin "30") (pinfunction "VCAP_1_30") (pintype "bidirectional"))
    )
    (net (code "96") (name "unconnected-(U$8-D4-Pad7)") (class "Default")
      (node (ref "U$8") (pin "7") (pinfunction "D4_7") (pintype "bidirectional"))
    )
    (net (code "97") (name "unconnected-(U$8-S4-Pad6)") (class "Default")
      (node (ref "U$8") (pin "6") (pinfunction "S4_6") (pintype "bidirectional"))
    )
    (net (code "98") (name "unconnected-(U$8-SEL4-Pad8)") (class "Default")
      (node (ref "U$8") (pin "8") (pinfunction "SEL4_8") (pintype "bidirectional"))
    )
    (net (code "99") (name "unconnected-(U$11-D4-Pad7)") (class "Default")
      (node (ref "U$11") (pin "7") (pinfunction "D4_7") (pintype "bidirectional"))
    )
    (net (code "100") (name "unconnected-(U$11-S4-Pad6)") (class "Default")
      (node (ref "U$11") (pin "6") (pinfunction "S4_6") (pintype "bidirectional"))
    )
    (net (code "101") (name "unconnected-(U$11-SEL4-Pad8)") (class "Default")
      (node (ref "U$11") (pin "8") (pinfunction "SEL4_8") (pintype "bidirectional"))
    )
    (net (code "102") (name "unconnected-(U$12-D4-Pad7)") (class "Default")
      (node (ref "U$12") (pin "7") (pinfunction "D4_7") (pintype "bidirectional"))
    )
    (net (code "103") (name "unconnected-(U$12-S4-Pad6)") (class "Default")
      (node (ref "U$12") (pin "6") (pinfunction "S4_6") (pintype "bidirectional"))
    )
    (net (code "104") (name "unconnected-(U$12-SEL4-Pad8)") (class "Default")
      (node (ref "U$12") (pin "8") (pinfunction "SEL4_8") (pintype "bidirectional"))
    )
  )
)
